# LEDS_Status.net
KiCad netlist of a schematic drawn in Altium Designer
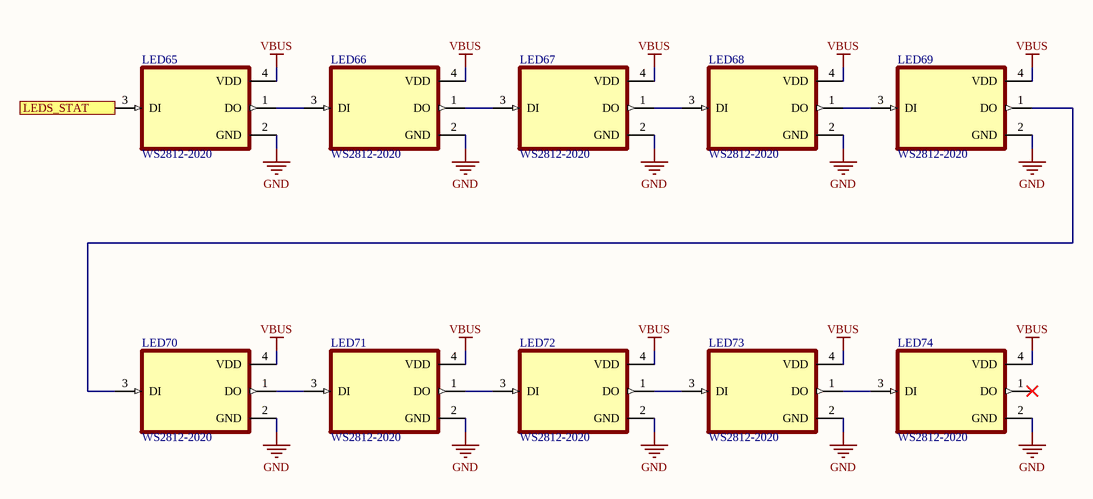
[diagram p0: LEDS_Status.SchDoc]

(export (version "E")
  (design (tool "Eeschema 10.0.6"))
  (components
    (comp (ref "LED65")
      (value "WS2812-2020")
      (footprint "LED_WS2812-2020")
      (description "Intelligent control LED light source, SMD-4")
      (fields (field (name "MF") "Worldsemi"))
      (libsource (lib "WS2812-2020") (part "WS2812-2020"))
    )
    (comp (ref "LED66")
      (value "WS2812-2020")
      (footprint "LED_WS2812-2020")
      (description "Intelligent control LED light source, SMD-4")
      (fields (field (name "MF") "Worldsemi"))
      (libsource (lib "WS2812-2020") (part "WS2812-2020"))
    )
    (comp (ref "LED67")
      (value "WS2812-2020")
      (footprint "LED_WS2812-2020")
      (description "Intelligent control LED light source, SMD-4")
      (fields (field (name "MF") "Worldsemi"))
      (libsource (lib "WS2812-2020") (part "WS2812-2020"))
    )
    (comp (ref "LED68")
      (value "WS2812-2020")
      (footprint "LED_WS2812-2020")
      (description "Intelligent control LED light source, SMD-4")
      (fields (field (name "MF") "Worldsemi"))
      (libsource (lib "WS2812-2020") (part "WS2812-2020"))
    )
    (comp (ref "LED69")
      (value "WS2812-2020")
      (footprint "LED_WS2812-2020")
      (description "Intelligent control LED light source, SMD-4")
      (fields (field (name "MF") "Worldsemi"))
      (libsource (lib "WS2812-2020") (part "WS2812-2020"))
    )
    (comp (ref "LED70")
      (value "WS2812-2020")
      (footprint "LED_WS2812-2020")
      (description "Intelligent control LED light source, SMD-4")
      (fields (field (name "MF") "Worldsemi"))
      (libsource (lib "WS2812-2020") (part "WS2812-2020"))
    )
    (comp (ref "LED71")
      (value "WS2812-2020")
      (footprint "LED_WS2812-2020")
      (description "Intelligent control LED light source, SMD-4")
      (fields (field (name "MF") "Worldsemi"))
      (libsource (lib "WS2812-2020") (part "WS2812-2020"))
    )
    (comp (ref "LED72")
      (value "WS2812-2020")
      (footprint "LED_WS2812-2020")
      (description "Intelligent control LED light source, SMD-4")
      (fields (field (name "MF") "Worldsemi"))
      (libsource (lib "WS2812-2020") (part "WS2812-2020"))
    )
    (comp (ref "LED73")
      (value "WS2812-2020")
      (footprint "LED_WS2812-2020")
      (description "Intelligent control LED light source, SMD-4")
      (fields (field (name "MF") "Worldsemi"))
      (libsource (lib "WS2812-2020") (part "WS2812-2020"))
    )
    (comp (ref "LED74")
      (value "WS2812-2020")
      (footprint "LED_WS2812-2020")
      (description "Intelligent control LED light source, SMD-4")
      (fields (field (name "MF") "Worldsemi"))
      (libsource (lib "WS2812-2020") (part "WS2812-2020"))
    )
  )
  (nets
    (net (code "1") (name "/LEDS_STAT") (class "Default")
      (node (ref "LED65") (pin "3") (pinfunction "DI_3") (pintype "input"))
    )
    (net (code "2") (name "GND") (class "Default")
      (node (ref "LED65") (pin "2") (pinfunction "GND_2") (pintype "power_in"))
      (node (ref "LED66") (pin "2") (pinfunction "GND_2") (pintype "power_in"))
      (node (ref "LED67") (pin "2") (pinfunction "GND_2") (pintype "power_in"))
      (node (ref "LED68") (pin "2") (pinfunction "GND_2") (pintype "power_in"))
      (node (ref "LED69") (pin "2") (pinfunction "GND_2") (pintype "power_in"))
      (node (ref "LED70") (pin "2") (pinfunction "GND_2") (pintype "power_in"))
      (node (ref "LED71") (pin "2") (pinfunction "GND_2") (pintype "power_in"))
      (node (ref "LED72") (pin "2") (pinfunction "GND_2") (pintype "power_in"))
      (node (ref "LED73") (pin "2") (pinfunction "GND_2") (pintype "power_in"))
      (node (ref "LED74") (pin "2") (pinfunction "GND_2") (pintype "power_in"))
    )
    (net (code "3") (name "Net-(LED65-DO)") (class "Default")
      (node (ref "LED65") (pin "1") (pinfunction "DO_1") (pintype "output"))
      (node (ref "LED66") (pin "3") (pinfunction "DI_3") (pintype "input"))
    )
    (net (code "4") (name "Net-(LED66-DO)") (class "Default")
      (node (ref "LED66") (pin "1") (pinfunction "DO_1") (pintype "output"))
      (node (ref "LED67") (pin "3") (pinfunction "DI_3") (pintype "input"))
    )
    (net (code "5") (name "Net-(LED67-DO)") (class "Default")
      (node (ref "LED67") (pin "1") (pinfunction "DO_1") (pintype "output"))
      (node (ref "LED68") (pin "3") (pinfunction "DI_3") (pintype "input"))
    )
    (net (code "6") (name "Net-(LED68-DO)") (class "Default")
      (node (ref "LED68") (pin "1") (pinfunction "DO_1") (pintype "output"))
      (node (ref "LED69") (pin "3") (pinfunction "DI_3") (pintype "input"))
    )
    (net (code "7") (name "Net-(LED69-DO)") (class "Default")
      (node (ref "LED69") (pin "1") (pinfunction "DO_1") (pintype "output"))
      (node (ref "LED70") (pin "3") (pinfunction "DI_3") (pintype "input"))
    )
    (net (code "8") (name "Net-(LED70-DO)") (class "Default")
      (node (ref "LED70") (pin "1") (pinfunction "DO_1") (pintype "output"))
      (node (ref "LED71") (pin "3") (pinfunction "DI_3") (pintype "input"))
    )
    (net (code "9") (name "Net-(LED71-DO)") (class "Default")
      (node (ref "LED71") (pin "1") (pinfunction "DO_1") (pintype "output"))
      (node (ref "LED72") (pin "3") (pinfunction "DI_3") (pintype "input"))
    )
    (net (code "10") (name "Net-(LED72-DO)") (class "Default")
      (node (ref "LED72") (pin "1") (pinfunction "DO_1") (pintype "output"))
      (node (ref "LED73") (pin "3") (pinfunction "DI_3") (pintype "input"))
    )
    (net (code "11") (name "Net-(LED73-DO)") (class "Default")
      (node (ref "LED73") (pin "1") (pinfunction "DO_1") (pintype "output"))
      (node (ref "LED74") (pin "3") (pinfunction "DI_3") (pintype "input"))
    )
    (net (code "12") (name "VBUS") (class "Default")
      (node (ref "LED65") (pin "4") (pinfunction "VDD_4") (pintype "power_in"))
      (node (ref "LED66") (pin "4") (pinfunction "VDD_4") (pintype "power_in"))
      (node (ref "LED67") (pin "4") (pinfunction "VDD_4") (pintype "power_in"))
      (node (ref "LED68") (pin "4") (pinfunction "VDD_4") (pintype "power_in"))
      (node (ref "LED69") (pin "4") (pinfunction "VDD_4") (pintype "power_in"))
      (node (ref "LED70") (pin "4") (pinfunction "VDD_4") (pintype "power_in"))
      (node (ref "LED71") (pin "4") (pinfunction "VDD_4") (pintype "power_in"))
      (node (ref "LED72") (pin "4") (pinfunction "VDD_4") (pintype "power_in"))
      (node (ref "LED73") (pin "4") (pinfunction "VDD_4") (pintype "power_in"))
      (node (ref "LED74") (pin "4") (pinfunction "VDD_4") (pintype "power_in"))
    )
    (net (code "13") (name "unconnected-(LED74-DO-Pad1)") (class "Default")
      (node (ref "LED74") (pin "1") (pinfunction "DO_1") (pintype "output+no_connect"))
    )
  )
)
